# IN-2-Module.net
KiCad netlist of a schematic drawn in EAGLE
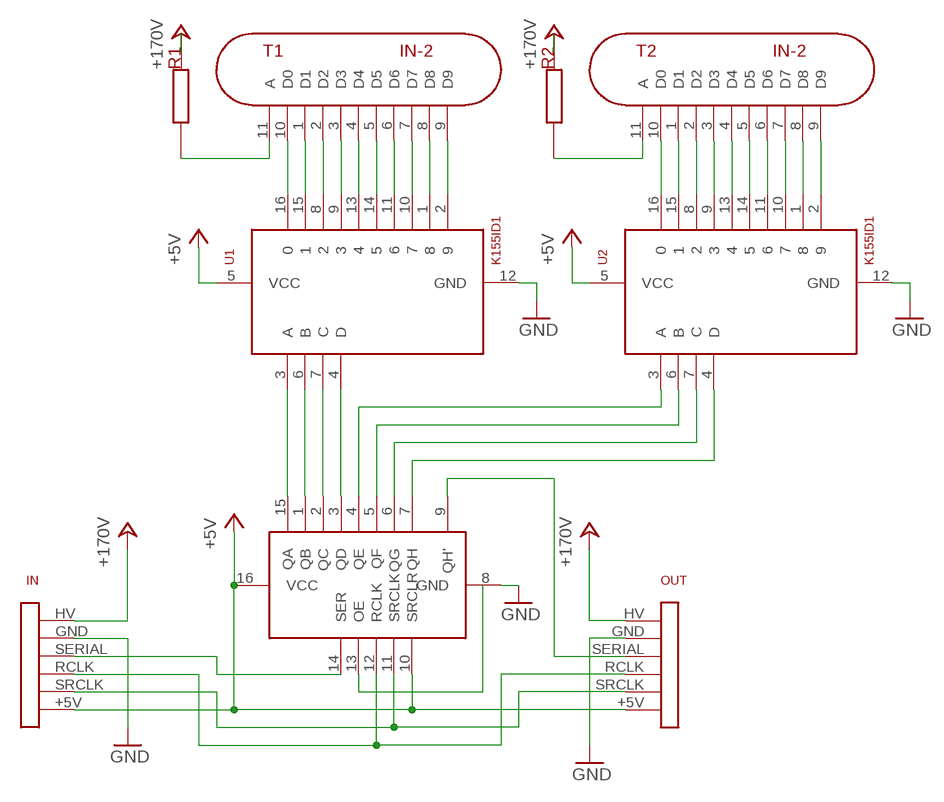
[diagram p0: schematic, sheet 1]

(export (version "E")
  (design (tool "Eeschema 10.0.6"))
  (components
    (comp (ref "IN")
      (value "NIXIE_INTERCONNECTLEFT")
      (footprint "eagle-import:NIXIE_INTERCONNECT_LEFT")
      (libsource (lib "eagle-import") (part "NIXIE_INTERCONNECTLEFT"))
    )
    (comp (ref "OUT")
      (value "NIXIE_INTERCONNECTRIGHT")
      (footprint "eagle-import:NIXIE_INTERCONNECT_RIGHT")
      (libsource (lib "eagle-import") (part "NIXIE_INTERCONNECTRIGHT"))
    )
    (comp (ref "R1")
      (value "22k")
      (footprint "eagle-import:ANODE_RESISTOR")
      (libsource (lib "eagle-import") (part "ANODE_RESISTOR"))
    )
    (comp (ref "R2")
      (value "22k")
      (footprint "eagle-import:ANODE_RESISTOR")
      (libsource (lib "eagle-import") (part "ANODE_RESISTOR"))
    )
    (comp (ref "T1")
      (value "IN-2")
      (footprint "eagle-import:IN-2")
      (libsource (lib "eagle-import") (part "IN-2"))
    )
    (comp (ref "T2")
      (value "IN-2")
      (footprint "eagle-import:IN-2")
      (libsource (lib "eagle-import") (part "IN-2"))
    )
    (comp (ref "U1")
      (value "K155ID1")
      (footprint "eagle-import:DIP16-2.54-19.2X7.62MM")
      (libsource (lib "eagle-import") (part "K155ID1"))
    )
    (comp (ref "U2")
      (value "K155ID1")
      (footprint "eagle-import:DIP16-2.54-19.2X7.62MM")
      (libsource (lib "eagle-import") (part "K155ID1"))
    )
    (comp (ref "U3")
      (value "74HC595")
      (footprint "eagle-import:DIL16")
      (libsource (lib "eagle-import") (part "74HC595"))
    )
  )
  (nets
    (net (code "1") (name "+5V") (class "Default")
      (node (ref "IN") (pin "+5V") (pinfunction "+5V_+5V") (pintype "bidirectional"))
      (node (ref "OUT") (pin "+5V") (pinfunction "+5V_+5V") (pintype "bidirectional"))
      (node (ref "U1") (pin "5") (pinfunction "VCC_5") (pintype "bidirectional"))
      (node (ref "U2") (pin "5") (pinfunction "VCC_5") (pintype "bidirectional"))
      (node (ref "U3") (pin "10") (pinfunction "SRCLR_10") (pintype "bidirectional"))
      (node (ref "U3") (pin "16") (pinfunction "VCC_16") (pintype "bidirectional"))
    )
    (net (code "2") (name "+170V") (class "Default")
      (node (ref "IN") (pin "HV") (pinfunction "HV_HV") (pintype "bidirectional"))
      (node (ref "OUT") (pin "HV") (pinfunction "HV_HV") (pintype "bidirectional"))
      (node (ref "R1") (pin "P$2") (pinfunction "P$2_P$2") (pintype "bidirectional"))
      (node (ref "R2") (pin "P$2") (pinfunction "P$2_P$2") (pintype "bidirectional"))
    )
    (net (code "3") (name "GND") (class "Default")
      (node (ref "IN") (pin "GND") (pinfunction "GND_GND") (pintype "bidirectional"))
      (node (ref "OUT") (pin "GND") (pinfunction "GND_GND") (pintype "bidirectional"))
      (node (ref "U1") (pin "12") (pinfunction "GND_12") (pintype "bidirectional"))
      (node (ref "U2") (pin "12") (pinfunction "GND_12") (pintype "bidirectional"))
      (node (ref "U3") (pin "8") (pinfunction "GND_8") (pintype "bidirectional"))
    )
    (net (code "4") (name "Net-(T1-A)") (class "Default")
      (node (ref "R1") (pin "P$1") (pinfunction "P$1_P$1") (pintype "bidirectional"))
      (node (ref "T1") (pin "11") (pinfunction "A_11") (pintype "bidirectional"))
    )
    (net (code "5") (name "Net-(T1-D0)") (class "Default")
      (node (ref "T1") (pin "10") (pinfunction "D0_10") (pintype "bidirectional"))
      (node (ref "U1") (pin "16") (pinfunction "0_16") (pintype "bidirectional"))
    )
    (net (code "6") (name "Net-(T1-D1)") (class "Default")
      (node (ref "T1") (pin "1") (pinfunction "D1_1") (pintype "bidirectional"))
      (node (ref "U1") (pin "15") (pinfunction "1_15") (pintype "bidirectional"))
    )
    (net (code "7") (name "Net-(T1-D2)") (class "Default")
      (node (ref "T1") (pin "2") (pinfunction "D2_2") (pintype "bidirectional"))
      (node (ref "U1") (pin "8") (pinfunction "2_8") (pintype "bidirectional"))
    )
    (net (code "8") (name "Net-(T1-D3)") (class "Default")
      (node (ref "T1") (pin "3") (pinfunction "D3_3") (pintype "bidirectional"))
      (node (ref "U1") (pin "9") (pinfunction "3_9") (pintype "bidirectional"))
    )
    (net (code "9") (name "Net-(T1-D4)") (class "Default")
      (node (ref "T1") (pin "4") (pinfunction "D4_4") (pintype "bidirectional"))
      (node (ref "U1") (pin "13") (pinfunction "4_13") (pintype "bidirectional"))
    )
    (net (code "10") (name "Net-(T1-D5)") (class "Default")
      (node (ref "T1") (pin "5") (pinfunction "D5_5") (pintype "bidirectional"))
      (node (ref "U1") (pin "14") (pinfunction "5_14") (pintype "bidirectional"))
    )
    (net (code "11") (name "Net-(T1-D6)") (class "Default")
      (node (ref "T1") (pin "6") (pinfunction "D6_6") (pintype "bidirectional"))
      (node (ref "U1") (pin "11") (pinfunction "6_11") (pintype "bidirectional"))
    )
    (net (code "12") (name "Net-(T1-D7)") (class "Default")
      (node (ref "T1") (pin "7") (pinfunction "D7_7") (pintype "bidirectional"))
      (node (ref "U1") (pin "10") (pinfunction "7_10") (pintype "bidirectional"))
    )
    (net (code "13") (name "Net-(T1-D8)") (class "Default")
      (node (ref "T1") (pin "8") (pinfunction "D8_8") (pintype "bidirectional"))
      (node (ref "U1") (pin "1") (pinfunction "8_1") (pintype "bidirectional"))
    )
    (net (code "14") (name "Net-(T1-D9)") (class "Default")
      (node (ref "T1") (pin "9") (pinfunction "D9_9") (pintype "bidirectional"))
      (node (ref "U1") (pin "2") (pinfunction "9_2") (pintype "bidirectional"))
    )
    (net (code "15") (name "Net-(T2-A)") (class "Default")
      (node (ref "R2") (pin "P$1") (pinfunction "P$1_P$1") (pintype "bidirectional"))
      (node (ref "T2") (pin "11") (pinfunction "A_11") (pintype "bidirectional"))
    )
    (net (code "16") (name "Net-(T2-D0)") (class "Default")
      (node (ref "T2") (pin "10") (pinfunction "D0_10") (pintype "bidirectional"))
      (node (ref "U2") (pin "16") (pinfunction "0_16") (pintype "bidirectional"))
    )
    (net (code "17") (name "Net-(T2-D1)") (class "Default")
      (node (ref "T2") (pin "1") (pinfunction "D1_1") (pintype "bidirectional"))
      (node (ref "U2") (pin "15") (pinfunction "1_15") (pintype "bidirectional"))
    )
    (net (code "18") (name "Net-(T2-D2)") (class "Default")
      (node (ref "T2") (pin "2") (pinfunction "D2_2") (pintype "bidirectional"))
      (node (ref "U2") (pin "8") (pinfunction "2_8") (pintype "bidirectional"))
    )
    (net (code "19") (name "Net-(T2-D3)") (class "Default")
      (node (ref "T2") (pin "3") (pinfunction "D3_3") (pintype "bidirectional"))
      (node (ref "U2") (pin "9") (pinfunction "3_9") (pintype "bidirectional"))
    )
    (net (code "20") (name "Net-(T2-D4)") (class "Default")
      (node (ref "T2") (pin "4") (pinfunction "D4_4") (pintype "bidirectional"))
      (node (ref "U2") (pin "13") (pinfunction "4_13") (pintype "bidirectional"))
    )
    (net (code "21") (name "Net-(T2-D5)") (class "Default")
      (node (ref "T2") (pin "5") (pinfunction "D5_5") (pintype "bidirectional"))
      (node (ref "U2") (pin "14") (pinfunction "5_14") (pintype "bidirectional"))
    )
    (net (code "22") (name "Net-(T2-D6)") (class "Default")
      (node (ref "T2") (pin "6") (pinfunction "D6_6") (pintype "bidirectional"))
      (node (ref "U2") (pin "11") (pinfunction "6_11") (pintype "bidirectional"))
    )
    (net (code "23") (name "Net-(T2-D7)") (class "Default")
      (node (ref "T2") (pin "7") (pinfunction "D7_7") (pintype "bidirectional"))
      (node (ref "U2") (pin "10") (pinfunction "7_10") (pintype "bidirectional"))
    )
    (net (code "24") (name "Net-(T2-D8)") (class "Default")
      (node (ref "T2") (pin "8") (pinfunction "D8_8") (pintype "bidirectional"))
      (node (ref "U2") (pin "1") (pinfunction "8_1") (pintype "bidirectional"))
    )
    (net (code "25") (name "Net-(T2-D9)") (class "Default")
      (node (ref "T2") (pin "9") (pinfunction "D9_9") (pintype "bidirectional"))
      (node (ref "U2") (pin "2") (pinfunction "9_2") (pintype "bidirectional"))
    )
    (net (code "26") (name "Net-(U1-A)") (class "Default")
      (node (ref "U1") (pin "3") (pinfunction "A_3") (pintype "bidirectional"))
      (node (ref "U3") (pin "15") (pinfunction "QA_15") (pintype "bidirectional"))
    )
    (net (code "27") (name "Net-(U1-B)") (class "Default")
      (node (ref "U1") (pin "6") (pinfunction "B_6") (pintype "bidirectional"))
      (node (ref "U3") (pin "1") (pinfunction "QB_1") (pintype "bidirectional"))
    )
    (net (code "28") (name "Net-(U1-C)") (class "Default")
      (node (ref "U1") (pin "7") (pinfunction "C_7") (pintype "bidirectional"))
      (node (ref "U3") (pin "2") (pinfunction "QC_2") (pintype "bidirectional"))
    )
    (net (code "29") (name "Net-(U1-D)") (class "Default")
      (node (ref "U1") (pin "4") (pinfunction "D_4") (pintype "bidirectional"))
      (node (ref "U3") (pin "3") (pinfunction "QD_3") (pintype "bidirectional"))
    )
    (net (code "30") (name "Net-(U2-A)") (class "Default")
      (node (ref "U2") (pin "3") (pinfunction "A_3") (pintype "bidirectional"))
      (node (ref "U3") (pin "4") (pinfunction "QE_4") (pintype "bidirectional"))
    )
    (net (code "31") (name "Net-(U2-B)") (class "Default")
      (node (ref "U2") (pin "6") (pinfunction "B_6") (pintype "bidirectional"))
      (node (ref "U3") (pin "5") (pinfunction "QF_5") (pintype "bidirectional"))
    )
    (net (code "32") (name "Net-(U2-C)") (class "Default")
      (node (ref "U2") (pin "7") (pinfunction "C_7") (pintype "bidirectional"))
      (node (ref "U3") (pin "6") (pinfunction "QG_6") (pintype "bidirectional"))
    )
    (net (code "33") (name "Net-(U2-D)") (class "Default")
      (node (ref "U2") (pin "4") (pinfunction "D_4") (pintype "bidirectional"))
      (node (ref "U3") (pin "7") (pinfunction "QH_7") (pintype "bidirectional"))
    )
    (net (code "34") (name "Net-(U3-QH')") (class "Default")
      (node (ref "OUT") (pin "SERIAL") (pinfunction "SERIAL_SERIAL") (pintype "bidirectional"))
      (node (ref "U3") (pin "9") (pinfunction "QH'_9") (pintype "bidirectional"))
    )
    (net (code "35") (name "Net-(U3-RCLK)") (class "Default")
      (node (ref "IN") (pin "RCLK") (pinfunction "RCLK_RCLK") (pintype "bidirectional"))
      (node (ref "OUT") (pin "RCLK") (pinfunction "RCLK_RCLK") (pintype "bidirectional"))
      (node (ref "U3") (pin "12") (pinfunction "RCLK_12") (pintype "bidirectional"))
    )
    (net (code "36") (name "Net-(U3-SER)") (class "Default")
      (node (ref "IN") (pin "SERIAL") (pinfunction "SERIAL_SERIAL") (pintype "bidirectional"))
      (node (ref "U3") (pin "14") (pinfunction "SER_14") (pintype "bidirectional"))
    )
    (net (code "37") (name "Net-(U3-SRCLK)") (class "Default")
      (node (ref "IN") (pin "SRCLK") (pinfunction "SRCLK_SRCLK") (pintype "bidirectional"))
      (node (ref "OUT") (pin "SRCLK") (pinfunction "SRCLK_SRCLK") (pintype "bidirectional"))
      (node (ref "U3") (pin "11") (pinfunction "SRCLK_11") (pintype "bidirectional"))
    )
    (net (code "38") (name "unconnected-(U3-OE-Pad13)") (class "Default")
      (node (ref "U3") (pin "13") (pinfunction "OE_13") (pintype "bidirectional"))
    )
  )
)
